# PCM2707.net
KiCad netlist of a schematic drawn in EAGLE
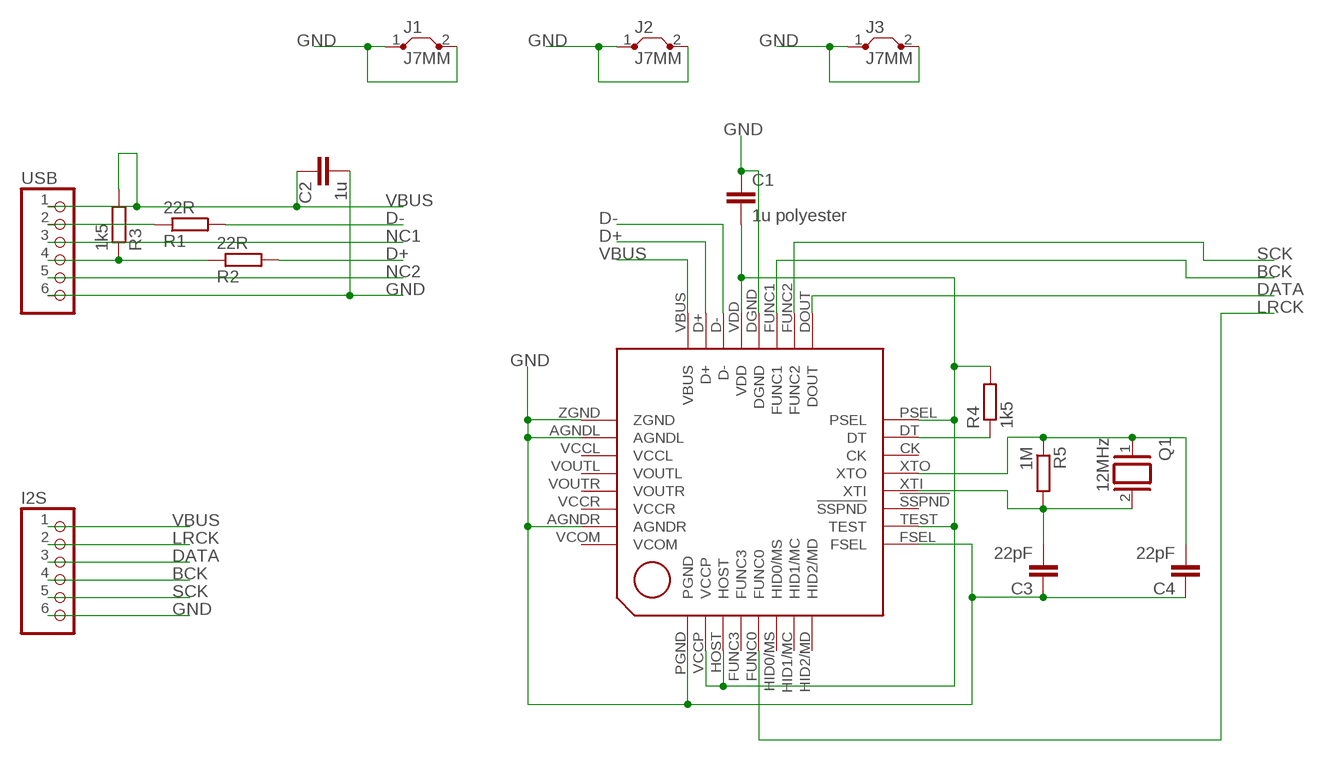
[diagram p0: schematic, sheet 1]

(export (version "E")
  (design (tool "Eeschema 10.0.6"))
  (components
    (comp (ref "C1")
      (value "1u polyester")
      (footprint "eagle-import:C5B4.5")
      (libsource (lib "eagle-import") (part "C5/4.5"))
    )
    (comp (ref "C2")
      (value "1u")
      (footprint "eagle-import:C5B3.5")
      (libsource (lib "eagle-import") (part "C5/3.5"))
    )
    (comp (ref "C3")
      (value "22pF")
      (footprint "eagle-import:C5B3.5")
      (libsource (lib "eagle-import") (part "C5/3.5"))
    )
    (comp (ref "C4")
      (value "22pF")
      (footprint "eagle-import:C5B3.5")
      (libsource (lib "eagle-import") (part "C5/3.5"))
    )
    (comp (ref "I2S")
      (value "PINHD-1X6/90")
      (footprint "eagle-import:1X06_90")
      (libsource (lib "eagle-import") (part "PINHD-1X6/90"))
    )
    (comp (ref "J1")
      (value "J7MM")
      (footprint "eagle-import:07")
      (libsource (lib "eagle-import") (part "J7MM"))
    )
    (comp (ref "J2")
      (value "J7MM")
      (footprint "eagle-import:07")
      (libsource (lib "eagle-import") (part "J7MM"))
    )
    (comp (ref "J3")
      (value "J7MM")
      (footprint "eagle-import:07")
      (libsource (lib "eagle-import") (part "J7MM"))
    )
    (comp (ref "Q1")
      (value "12MHz")
      (footprint "eagle-import:Q")
      (libsource (lib "eagle-import") (part "XTAL"))
    )
    (comp (ref "R1")
      (value "22R")
      (footprint "eagle-import:0207_7")
      (libsource (lib "eagle-import") (part "R-EU_0207/7"))
    )
    (comp (ref "R2")
      (value "22R")
      (footprint "eagle-import:0207_7")
      (libsource (lib "eagle-import") (part "R-EU_0207/7"))
    )
    (comp (ref "R3")
      (value "1k5")
      (footprint "eagle-import:0207_7")
      (libsource (lib "eagle-import") (part "R-EU_0207/7"))
    )
    (comp (ref "R4")
      (value "1k5")
      (footprint "eagle-import:0207_7")
      (libsource (lib "eagle-import") (part "R-EU_0207/7"))
    )
    (comp (ref "R5")
      (value "1M")
      (footprint "eagle-import:0207_7")
      (libsource (lib "eagle-import") (part "R-EU_0207/7"))
    )
    (comp (ref "U$1")
      (value "PCM2706")
      (footprint "eagle-import:TQFP32-08")
      (libsource (lib "eagle-import") (part "PCM2706"))
    )
    (comp (ref "USB")
      (value "PINHD-1X6")
      (footprint "eagle-import:1X06")
      (libsource (lib "eagle-import") (part "PINHD-1X6"))
    )
  )
  (nets
    (net (code "1") (name "/BCK") (class "Default")
      (node (ref "I2S") (pin "4") (pinfunction "4_4") (pintype "passive"))
      (node (ref "U$1") (pin "FUNC1") (pinfunction "FUNC1_FUNC1") (pintype "bidirectional"))
    )
    (net (code "2") (name "/D+") (class "Default")
      (node (ref "R2") (pin "2") (pinfunction "2_2") (pintype "passive"))
      (node (ref "U$1") (pin "D+") (pinfunction "D+_D+") (pintype "bidirectional"))
    )
    (net (code "3") (name "/D-") (class "Default")
      (node (ref "R1") (pin "2") (pinfunction "2_2") (pintype "passive"))
      (node (ref "U$1") (pin "D-") (pinfunction "D-_D-") (pintype "bidirectional"))
    )
    (net (code "4") (name "/DATA") (class "Default")
      (node (ref "I2S") (pin "3") (pinfunction "3_3") (pintype "passive"))
      (node (ref "U$1") (pin "DOUT") (pinfunction "DOUT_DOUT") (pintype "bidirectional"))
    )
    (net (code "5") (name "/GND") (class "Default")
      (node (ref "C1") (pin "1") (pinfunction "1_1") (pintype "passive"))
      (node (ref "C2") (pin "2") (pinfunction "2_2") (pintype "passive"))
      (node (ref "C3") (pin "1") (pinfunction "1_1") (pintype "passive"))
      (node (ref "C4") (pin "1") (pinfunction "1_1") (pintype "passive"))
      (node (ref "I2S") (pin "6") (pinfunction "6_6") (pintype "passive"))
      (node (ref "J1") (pin "1") (pinfunction "1_1") (pintype "passive"))
      (node (ref "J1") (pin "2") (pinfunction "2_2") (pintype "passive"))
      (node (ref "J2") (pin "1") (pinfunction "1_1") (pintype "passive"))
      (node (ref "J2") (pin "2") (pinfunction "2_2") (pintype "passive"))
      (node (ref "J3") (pin "1") (pinfunction "1_1") (pintype "passive"))
      (node (ref "J3") (pin "2") (pinfunction "2_2") (pintype "passive"))
      (node (ref "U$1") (pin "AGNDL") (pinfunction "AGNDL_AGNDL") (pintype "power_in"))
      (node (ref "U$1") (pin "AGNDR") (pinfunction "AGNDR_AGNDR") (pintype "power_in"))
      (node (ref "U$1") (pin "DGND") (pinfunction "DGND_DGND") (pintype "power_in"))
      (node (ref "U$1") (pin "FSEL") (pinfunction "FSEL_FSEL") (pintype "bidirectional"))
      (node (ref "U$1") (pin "PGND") (pinfunction "PGND_PGND") (pintype "power_in"))
      (node (ref "U$1") (pin "ZGND") (pinfunction "ZGND_ZGND") (pintype "power_in"))
      (node (ref "USB") (pin "6") (pinfunction "6_6") (pintype "passive"))
    )
    (net (code "6") (name "/LRCK") (class "Default")
      (node (ref "I2S") (pin "2") (pinfunction "2_2") (pintype "passive"))
      (node (ref "U$1") (pin "FUNC0") (pinfunction "FUNC0_FUNC0") (pintype "bidirectional"))
    )
    (net (code "7") (name "/NC1") (class "Default")
      (node (ref "USB") (pin "3") (pinfunction "3_3") (pintype "passive"))
    )
    (net (code "8") (name "/NC2") (class "Default")
      (node (ref "USB") (pin "5") (pinfunction "5_5") (pintype "passive"))
    )
    (net (code "9") (name "/SCK") (class "Default")
      (node (ref "I2S") (pin "5") (pinfunction "5_5") (pintype "passive"))
      (node (ref "U$1") (pin "FUNC2") (pinfunction "FUNC2_FUNC2") (pintype "bidirectional"))
    )
    (net (code "10") (name "/VBUS") (class "Default")
      (node (ref "C2") (pin "1") (pinfunction "1_1") (pintype "passive"))
      (node (ref "I2S") (pin "1") (pinfunction "1_1") (pintype "passive"))
      (node (ref "R3") (pin "2") (pinfunction "2_2") (pintype "passive"))
      (node (ref "U$1") (pin "VBUS") (pinfunction "VBUS_VBUS") (pintype "power_in"))
      (node (ref "USB") (pin "1") (pinfunction "1_1") (pintype "passive"))
    )
    (net (code "11") (name "/VCCL") (class "Default")
      (node (ref "U$1") (pin "VCCL") (pinfunction "VCCL_VCCL") (pintype "power_in"))
    )
    (net (code "12") (name "/VCCR") (class "Default")
      (node (ref "U$1") (pin "VCCR") (pinfunction "VCCR_VCCR") (pintype "power_in"))
    )
    (net (code "13") (name "/VCOM") (class "Default")
      (node (ref "U$1") (pin "VCOM") (pinfunction "VCOM_VCOM") (pintype "power_in"))
    )
    (net (code "14") (name "Net-(C1-Pad2)") (class "Default")
      (node (ref "C1") (pin "2") (pinfunction "2_2") (pintype "passive"))
      (node (ref "R4") (pin "2") (pinfunction "2_2") (pintype "passive"))
      (node (ref "U$1") (pin "HOST") (pinfunction "HOST_HOST") (pintype "power_in"))
      (node (ref "U$1") (pin "PSEL") (pinfunction "PSEL_PSEL") (pintype "bidirectional"))
      (node (ref "U$1") (pin "TEST") (pinfunction "TEST_TEST") (pintype "bidirectional"))
      (node (ref "U$1") (pin "VCCP") (pinfunction "VCCP_VCCP") (pintype "power_in"))
      (node (ref "U$1") (pin "VDD") (pinfunction "VDD_VDD") (pintype "power_in"))
    )
    (net (code "15") (name "Net-(C3-Pad2)") (class "Default")
      (node (ref "C3") (pin "2") (pinfunction "2_2") (pintype "passive"))
      (node (ref "Q1") (pin "2") (pinfunction "2_2") (pintype "passive"))
      (node (ref "R5") (pin "2") (pinfunction "2_2") (pintype "passive"))
      (node (ref "U$1") (pin "XTI") (pinfunction "XTI_XTI") (pintype "bidirectional"))
    )
    (net (code "16") (name "Net-(C4-Pad2)") (class "Default")
      (node (ref "C4") (pin "2") (pinfunction "2_2") (pintype "passive"))
      (node (ref "Q1") (pin "1") (pinfunction "1_1") (pintype "passive"))
      (node (ref "R5") (pin "1") (pinfunction "1_1") (pintype "passive"))
      (node (ref "U$1") (pin "XTO") (pinfunction "XTO_XTO") (pintype "bidirectional"))
    )
    (net (code "17") (name "Net-(R1-Pad1)") (class "Default")
      (node (ref "R1") (pin "1") (pinfunction "1_1") (pintype "passive"))
      (node (ref "USB") (pin "2") (pinfunction "2_2") (pintype "passive"))
    )
    (net (code "18") (name "Net-(R2-Pad1)") (class "Default")
      (node (ref "R2") (pin "1") (pinfunction "1_1") (pintype "passive"))
      (node (ref "R3") (pin "1") (pinfunction "1_1") (pintype "passive"))
      (node (ref "USB") (pin "4") (pinfunction "4_4") (pintype "passive"))
    )
    (net (code "19") (name "Net-(R4-Pad1)") (class "Default")
      (node (ref "R4") (pin "1") (pinfunction "1_1") (pintype "passive"))
      (node (ref "U$1") (pin "DT") (pinfunction "DT_DT") (pintype "bidirectional"))
    )
    (net (code "20") (name "unconnected-(U$1-PadCK)") (class "Default")
      (node (ref "U$1") (pin "CK") (pinfunction "CK_CK") (pintype "bidirectional"))
    )
    (net (code "21") (name "unconnected-(U$1-PadFUNC3)") (class "Default")
      (node (ref "U$1") (pin "FUNC3") (pinfunction "FUNC3_FUNC3") (pintype "bidirectional"))
    )
    (net (code "22") (name "unconnected-(U$1-PadHID0{slash}MS)") (class "Default")
      (node (ref "U$1") (pin "HID0/MS") (pinfunction "HID0/MS_HID0/MS") (pintype "bidirectional"))
    )
    (net (code "23") (name "unconnected-(U$1-PadHID1{slash}MC)") (class "Default")
      (node (ref "U$1") (pin "HID1/MC") (pinfunction "HID1/MC_HID1/MC") (pintype "bidirectional"))
    )
    (net (code "24") (name "unconnected-(U$1-PadHID2{slash}MD)") (class "Default")
      (node (ref "U$1") (pin "HID2/MD") (pinfunction "HID2/MD_HID2/MD") (pintype "bidirectional"))
    )
    (net (code "25") (name "unconnected-(U$1-PadVOUTL)") (class "Default")
      (node (ref "U$1") (pin "VOUTL") (pinfunction "VOUTL_VOUTL") (pintype "output"))
    )
    (net (code "26") (name "unconnected-(U$1-PadVOUTR)") (class "Default")
      (node (ref "U$1") (pin "VOUTR") (pinfunction "VOUTR_VOUTR") (pintype "output"))
    )
    (net (code "27") (name "unconnected-(U$1-~{SSPND}-Pad!SSPND)") (class "Default")
      (node (ref "U$1") (pin "!SSPND") (pinfunction "~{SSPND}_!SSPND") (pintype "bidirectional"))
    )
  )
)
